# ProPrj_SunLight_2026-07-09.net
KiCad netlist of a schematic drawn in EasyEDA Pro
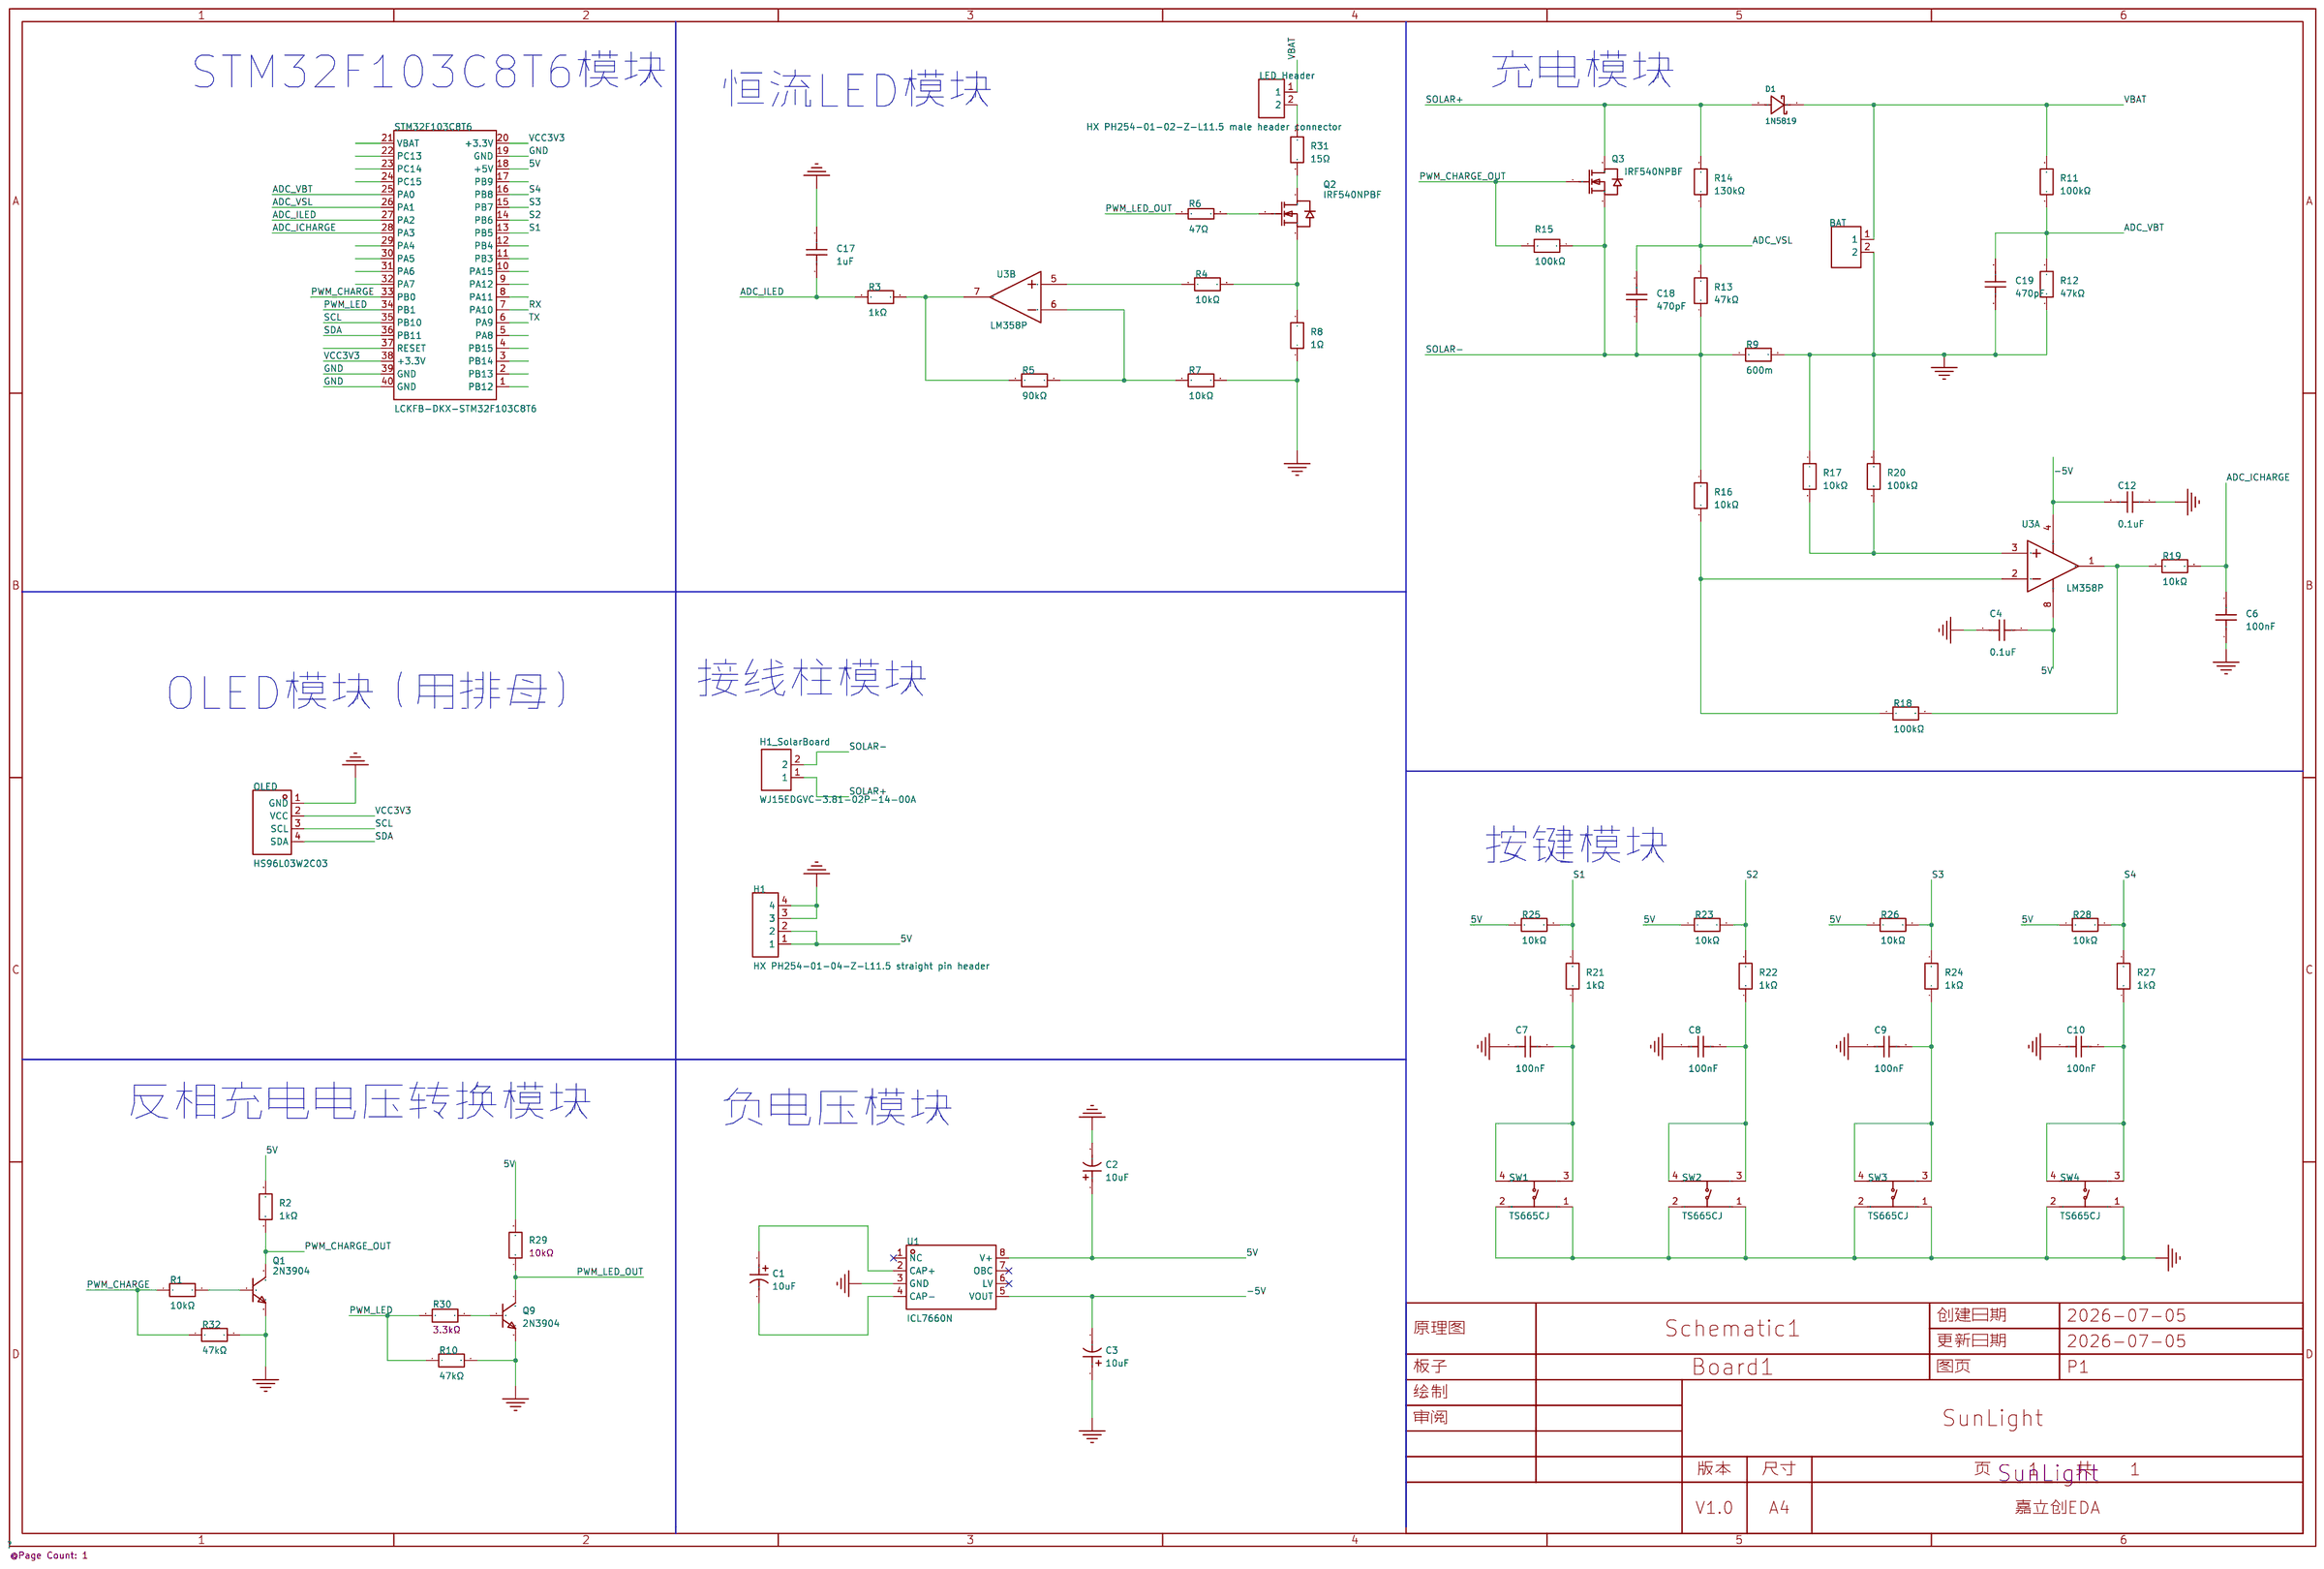
[diagram p0: schematic sheet]

(export (version "E")
  (design (tool "Eeschema 10.0.6"))
  (components
    (comp (ref "BAT")
      (value "WJ15EDGVC-3.81-02P-14-00A")
      (footprint "easyedapro:CONN-TH_WJ15EDGVC-3.81-2P")
      (fields (field (name "Manufacturer") "KANGNEX(康奈克斯电气)"))
      (libsource (lib "easyedapro") (part "WJ15EDGVC-3.81-2P"))
    )
    (comp (ref "C1")
      (value "10uF")
      (footprint "easyedapro:CAP-TH_BD10.0-P5.00-D0.6-FD_1")
      (fields (field (name "Manufacturer Part") "ERG450V10M10x16") (field (name "Manufacturer") "JIERR(捷而瑞)"))
      (libsource (lib "easyedapro") (part "ERG450V10M10X16"))
    )
    (comp (ref "C2")
      (value "10uF")
      (footprint "easyedapro:CAP-TH_BD10.0-P5.00-D0.6-FD_1")
      (fields (field (name "Manufacturer Part") "ERG450V10M10x16") (field (name "Manufacturer") "JIERR(捷而瑞)"))
      (libsource (lib "easyedapro") (part "ERG450V10M10X16"))
    )
    (comp (ref "C3")
      (value "10uF")
      (footprint "easyedapro:CAP-TH_BD10.0-P5.00-D0.6-FD_1")
      (fields (field (name "Manufacturer Part") "ERG450V10M10x16") (field (name "Manufacturer") "JIERR(捷而瑞)"))
      (libsource (lib "easyedapro") (part "ERG450V10M10X16"))
    )
    (comp (ref "C4")
      (value "0.1uF")
      (footprint "easyedapro:CAP-TH_L5.3-W3.2-P2.54-D0.6-S2.65")
      (description "容值:100nF;精度:-20%~+80%;额定电压:50V;温度系数:Y5V;")
      (fields
        (field (name "Manufacturer Part") "CC1H104ZA1ED3F5O1100")
        (field (name "Manufacturer") "Dersonic(德尔创)")
      )
      (libsource (lib "easyedapro") (part "CC1H104ZA1ED3F5O1100"))
    )
    (comp (ref "C6")
      (value "100nF")
      (footprint "easyedapro:CAP-TH_L5.5-W4.0-P5.00-D0.5")
      (fields
        (field (name "Manufacturer Part") "Y5P102K2KV16CC0224")
        (field (name "Manufacturer") "KNSCHA(科尼盛)")
      )
      (libsource (lib "easyedapro") (part "Y5P102K2KV16CC0224"))
    )
    (comp (ref "C7")
      (value "100nF")
      (footprint "easyedapro:CAP-TH_L5.5-W4.0-P5.00-D0.5")
      (fields
        (field (name "Manufacturer Part") "Y5P102K2KV16CC0224")
        (field (name "Manufacturer") "KNSCHA(科尼盛)")
      )
      (libsource (lib "easyedapro") (part "Y5P102K2KV16CC0224"))
    )
    (comp (ref "C8")
      (value "100nF")
      (footprint "easyedapro:CAP-TH_L5.5-W4.0-P5.00-D0.5")
      (fields
        (field (name "Manufacturer Part") "Y5P102K2KV16CC0224")
        (field (name "Manufacturer") "KNSCHA(科尼盛)")
      )
      (libsource (lib "easyedapro") (part "Y5P102K2KV16CC0224"))
    )
    (comp (ref "C9")
      (value "100nF")
      (footprint "easyedapro:CAP-TH_L5.5-W4.0-P5.00-D0.5")
      (fields
        (field (name "Manufacturer Part") "Y5P102K2KV16CC0224")
        (field (name "Manufacturer") "KNSCHA(科尼盛)")
      )
      (libsource (lib "easyedapro") (part "Y5P102K2KV16CC0224"))
    )
    (comp (ref "C10")
      (value "100nF")
      (footprint "easyedapro:CAP-TH_L5.5-W4.0-P5.00-D0.5")
      (fields
        (field (name "Manufacturer Part") "Y5P102K2KV16CC0224")
        (field (name "Manufacturer") "KNSCHA(科尼盛)")
      )
      (libsource (lib "easyedapro") (part "Y5P102K2KV16CC0224"))
    )
    (comp (ref "C12")
      (value "0.1uF")
      (footprint "easyedapro:CAP-TH_L5.3-W3.2-P2.54-D0.6-S2.65")
      (description "容值:100nF;精度:-20%~+80%;额定电压:50V;温度系数:Y5V;")
      (fields
        (field (name "Manufacturer Part") "CC1H104ZA1ED3F5O1100")
        (field (name "Manufacturer") "Dersonic(德尔创)")
      )
      (libsource (lib "easyedapro") (part "CC1H104ZA1ED3F5O1100"))
    )
    (comp (ref "C17")
      (value "1uF")
      (footprint "easyedapro:CAP-TH_L5.8-W2.8")
      (fields
        (field (name "Manufacturer Part") "CC1H104MC1FD3F6C10SA")
        (field (name "Manufacturer") "Dersonic(德尔创)")
      )
      (libsource (lib "easyedapro") (part "CC1H104MC1FD3F6C10SA"))
    )
    (comp (ref "C18")
      (value "470pF")
      (footprint "easyedapro:CAP-TH_L8.0-W4.5-P10.00-D1.2")
      (fields (field (name "Manufacturer Part") "A09B1D471KN0B0S0N0") (field (name "Manufacturer") "STE(松田)"))
      (libsource (lib "easyedapro") (part "A09B1D471KN0B0S0N0"))
    )
    (comp (ref "C19")
      (value "470pF")
      (footprint "easyedapro:CAP-TH_L5.5-W4.0-P5.00-D0.5")
      (fields
        (field (name "Manufacturer Part") "Y5P102K2KV16CC0224")
        (field (name "Manufacturer") "KNSCHA(科尼盛)")
      )
      (libsource (lib "easyedapro") (part "Y5P102K2KV16CC0224"))
    )
    (comp (ref "D1")
      (value "1N5819")
      (footprint "easyedapro:DO-41_BD2.4-L4.7-P8.70-D0.9-RD")
      (fields (field (name "Manufacturer") "R+O(宏嘉诚)"))
      (libsource (lib "easyedapro") (part "1N5819_C54795756"))
    )
    (comp (ref "H1")
      (value "HX PH254-01-04-Z-L11.5 straight pin header")
      (footprint "easyedapro:HDR-TH_4P-HX-PH254-01-04-Z-L11.5")
      (fields (field (name "Manufacturer") "hanxia(韩下)"))
      (libsource (lib "easyedapro") (part "HX PH254-01-04-Z-L11.5 STRAIGHT PIN HEADER"))
    )
    (comp (ref "H1_SolarBoard")
      (value "WJ15EDGVC-3.81-02P-14-00A")
      (footprint "easyedapro:CONN-TH_WJ15EDGVC-3.81-2P")
      (fields (field (name "Manufacturer") "KANGNEX(康奈克斯电气)"))
      (libsource (lib "easyedapro") (part "WJ15EDGVC-3.81-2P"))
    )
    (comp (ref "LED_Header")
      (value "HX PH254-01-02-Z-L11.5 male header connector")
      (footprint "easyedapro:HDR-TH_2P-P2.54-V-M")
      (fields (field (name "Manufacturer") "hanxia(韩下)"))
      (libsource (lib "easyedapro") (part "HX PH254-01-02-Z-L11.5 MALE HEADER CONNECTOR"))
    )
    (comp (ref "OLED")
      (value "HS96L03W2C03")
      (footprint "easyedapro:OLED-TH_L27.8-W27.2-P2.54_C9900033791")
      (description "核心芯片:SSD1315芯片;接口类型:I2C;尺寸(inch):0.96;像素分辨率:128x64;")
      (fields (field (name "Manufacturer") "HS(汉昇)"))
      (libsource (lib "easyedapro") (part "HS96L03W2C03"))
    )
    (comp (ref "Q1")
      (value "2N3904")
      (footprint "easyedapro:TO-92-3_L4.6-W3.6-P1.27-L_1")
      (fields (field (name "Manufacturer") "JSMSEMI(杰盛微)"))
      (libsource (lib "easyedapro") (part "2N3904_C2874602"))
    )
    (comp (ref "Q2")
      (value "IRF540NPBF")
      (footprint "easyedapro:TO-220-3_L10.0-W4.5-P2.54-L")
      (fields (field (name "Manufacturer") "Infineon(英飞凌)"))
      (libsource (lib "easyedapro") (part "IRF540NPBF"))
    )
    (comp (ref "Q3")
      (value "IRF540NPBF")
      (footprint "easyedapro:TO-220-3_L10.0-W4.5-P2.54-L")
      (fields (field (name "Manufacturer") "Infineon(英飞凌)"))
      (libsource (lib "easyedapro") (part "IRF540NPBF"))
    )
    (comp (ref "Q9")
      (value "2N3904")
      (footprint "easyedapro:TO-92-3_L4.6-W3.6-P1.27-L_1")
      (description "晶体管类型:NPN;集电极电流(Ic):200mA;集射极击穿电压(Vceo):40V;耗散功率(Pd):625mW;直流电流增益(hFE):-;")
      (fields (field (name "Manufacturer") "JSMSEMI(杰盛微)"))
      (libsource (lib "easyedapro") (part "2N3904_C2874602"))
    )
    (comp (ref "R1")
      (value "10kΩ")
      (footprint "easyedapro:RES-TH_BD2.7-L6.2-P10.20-D0.4")
      (description "电阻类型:金属膜电阻;阻值:1kΩ;精度:±1%;功率:250mW;温度系数:±100ppm/℃;")
      (fields (field (name "Manufacturer Part") "MF1/4W-1K±1%-ST52") (field (name "Manufacturer") "VO(翔胜)"))
      (libsource (lib "easyedapro") (part "MF1/4W-1K±1%-ST52"))
    )
    (comp (ref "R2")
      (value "1kΩ")
      (footprint "easyedapro:RES-TH_BD2.7-L6.2-P10.20-D0.4")
      (description "电阻类型:金属膜电阻;阻值:1kΩ;精度:±1%;功率:250mW;温度系数:±100ppm/℃;")
      (fields (field (name "Manufacturer Part") "MF1/4W-1K±1%-ST52") (field (name "Manufacturer") "VO(翔胜)"))
      (libsource (lib "easyedapro") (part "MF1/4W-1K±1%-ST52"))
    )
    (comp (ref "R3")
      (value "1kΩ")
      (footprint "easyedapro:RES-TH_BD2.7-L6.2-P10.20-D0.4")
      (description "电阻类型:金属膜电阻;阻值:1kΩ;精度:±1%;功率:250mW;温度系数:±100ppm/℃;")
      (fields (field (name "Manufacturer Part") "MF1/4W-1K±1%-ST52") (field (name "Manufacturer") "VO(翔胜)"))
      (libsource (lib "easyedapro") (part "MF1/4W-1K±1%-ST52"))
    )
    (comp (ref "R4")
      (value "10kΩ")
      (footprint "easyedapro:RES-TH_BD2.7-L6.2-P10.20-D0.4")
      (description "电阻类型:金属膜电阻;阻值:1kΩ;精度:±1%;功率:250mW;温度系数:±100ppm/℃;")
      (fields (field (name "Manufacturer Part") "MF1/4W-1K±1%-ST52") (field (name "Manufacturer") "VO(翔胜)"))
      (libsource (lib "easyedapro") (part "MF1/4W-1K±1%-ST52"))
    )
    (comp (ref "R5")
      (value "90kΩ")
      (footprint "easyedapro:RES-TH_BD2.7-L6.2-P10.20-D0.4")
      (description "电阻类型:金属膜电阻;阻值:1kΩ;精度:±1%;功率:250mW;温度系数:±100ppm/℃;")
      (fields (field (name "Manufacturer Part") "MF1/4W-1K±1%-ST52") (field (name "Manufacturer") "VO(翔胜)"))
      (libsource (lib "easyedapro") (part "MF1/4W-1K±1%-ST52"))
    )
    (comp (ref "R6")
      (value "47Ω")
      (footprint "easyedapro:RES-TH_BD2.4-L6.3-P10.30-D0.6")
      (fields (field (name "Manufacturer Part") "MFR-25FTE52-47R") (field (name "Manufacturer") "YAGEO(国巨)"))
      (libsource (lib "easyedapro") (part "MFR-25FTE52-47R"))
    )
    (comp (ref "R7")
      (value "10kΩ")
      (footprint "easyedapro:RES-TH_BD2.7-L6.2-P10.20-D0.4")
      (description "电阻类型:金属膜电阻;阻值:1kΩ;精度:±1%;功率:250mW;温度系数:±100ppm/℃;")
      (fields (field (name "Manufacturer Part") "MF1/4W-1K±1%-ST52") (field (name "Manufacturer") "VO(翔胜)"))
      (libsource (lib "easyedapro") (part "MF1/4W-1K±1%-ST52"))
    )
    (comp (ref "R8")
      (value "1Ω")
      (footprint "easyedapro:RES-TH_BD2.7-L6.2-P10.20-D0.4")
      (description "电阻类型:金属膜电阻;阻值:1kΩ;精度:±1%;功率:250mW;温度系数:±100ppm/℃;")
      (fields (field (name "Manufacturer Part") "MF1/4W-1K±1%-ST52") (field (name "Manufacturer") "VO(翔胜)"))
      (libsource (lib "easyedapro") (part "MF1/4W-1K±1%-ST52"))
    )
    (comp (ref "R9")
      (value "600m")
      (footprint "easyedapro:RES-TH_BD2.7-L6.2-P10.20-D0.4")
      (description "电阻类型:金属膜电阻;阻值:1kΩ;精度:±1%;功率:250mW;温度系数:±100ppm/℃;")
      (fields (field (name "Manufacturer Part") "MF1/4W-1K±1%-ST52") (field (name "Manufacturer") "VO(翔胜)"))
      (libsource (lib "easyedapro") (part "MF1/4W-1K±1%-ST52"))
    )
    (comp (ref "R10")
      (value "47kΩ")
      (footprint "easyedapro:RES-TH_BD2.7-L6.2-P10.20-D0.4")
      (fields (field (name "Manufacturer Part") "MF1/4W-47K±1%-ST52") (field (name "Manufacturer") "VO(翔胜)"))
      (libsource (lib "easyedapro") (part "MF1/4W-47K±1%-ST52"))
    )
    (comp (ref "R11")
      (value "100kΩ")
      (footprint "easyedapro:RES-TH_BD2.7-L6.2-P10.20-D0.4")
      (description "电阻类型:金属膜电阻;阻值:1kΩ;精度:±1%;功率:250mW;温度系数:±100ppm/℃;")
      (fields (field (name "Manufacturer Part") "MF1/4W-1K±1%-ST52") (field (name "Manufacturer") "VO(翔胜)"))
      (libsource (lib "easyedapro") (part "MF1/4W-1K±1%-ST52"))
    )
    (comp (ref "R12")
      (value "47kΩ")
      (footprint "easyedapro:RES-TH_BD2.7-L6.2-P10.20-D0.4")
      (description "电阻类型:金属膜电阻;阻值:1kΩ;精度:±1%;功率:250mW;温度系数:±100ppm/℃;")
      (fields (field (name "Manufacturer Part") "MF1/4W-1K±1%-ST52") (field (name "Manufacturer") "VO(翔胜)"))
      (libsource (lib "easyedapro") (part "MF1/4W-1K±1%-ST52"))
    )
    (comp (ref "R13")
      (value "47kΩ")
      (footprint "easyedapro:RES-TH_BD2.7-L6.2-P10.20-D0.4")
      (description "电阻类型:金属膜电阻;阻值:1kΩ;精度:±1%;功率:250mW;温度系数:±100ppm/℃;")
      (fields (field (name "Manufacturer Part") "MF1/4W-1K±1%-ST52") (field (name "Manufacturer") "VO(翔胜)"))
      (libsource (lib "easyedapro") (part "MF1/4W-1K±1%-ST52"))
    )
    (comp (ref "R14")
      (value "130kΩ")
      (footprint "easyedapro:RES-TH_BD2.7-L6.2-P10.20-D0.4")
      (description "电阻类型:金属膜电阻;阻值:1kΩ;精度:±1%;功率:250mW;温度系数:±100ppm/℃;")
      (fields (field (name "Manufacturer Part") "MF1/4W-1K±1%-ST52") (field (name "Manufacturer") "VO(翔胜)"))
      (libsource (lib "easyedapro") (part "MF1/4W-1K±1%-ST52"))
    )
    (comp (ref "R15")
      (value "100kΩ")
      (footprint "easyedapro:RES-TH_BD2.7-L6.2-P10.20-D0.4")
      (description "电阻类型:金属膜电阻;阻值:1kΩ;精度:±1%;功率:250mW;温度系数:±100ppm/℃;")
      (fields (field (name "Manufacturer Part") "MF1/4W-1K±1%-ST52") (field (name "Manufacturer") "VO(翔胜)"))
      (libsource (lib "easyedapro") (part "MF1/4W-1K±1%-ST52"))
    )
    (comp (ref "R16")
      (value "10kΩ")
      (footprint "easyedapro:RES-TH_BD2.7-L6.2-P10.20-D0.4")
      (description "电阻类型:金属膜电阻;阻值:1kΩ;精度:±1%;功率:250mW;温度系数:±100ppm/℃;")
      (fields (field (name "Manufacturer Part") "MF1/4W-1K±1%-ST52") (field (name "Manufacturer") "VO(翔胜)"))
      (libsource (lib "easyedapro") (part "MF1/4W-1K±1%-ST52"))
    )
    (comp (ref "R17")
      (value "10kΩ")
      (footprint "easyedapro:RES-TH_BD2.7-L6.2-P10.20-D0.4")
      (description "电阻类型:金属膜电阻;阻值:1kΩ;精度:±1%;功率:250mW;温度系数:±100ppm/℃;")
      (fields (field (name "Manufacturer Part") "MF1/4W-1K±1%-ST52") (field (name "Manufacturer") "VO(翔胜)"))
      (libsource (lib "easyedapro") (part "MF1/4W-1K±1%-ST52"))
    )
    (comp (ref "R18")
      (value "100kΩ")
      (footprint "easyedapro:RES-TH_BD2.7-L6.2-P10.20-D0.4")
      (description "电阻类型:金属膜电阻;阻值:1kΩ;精度:±1%;功率:250mW;温度系数:±100ppm/℃;")
      (fields (field (name "Manufacturer Part") "MF1/4W-1K±1%-ST52") (field (name "Manufacturer") "VO(翔胜)"))
      (libsource (lib "easyedapro") (part "MF1/4W-1K±1%-ST52"))
    )
    (comp (ref "R19")
      (value "10kΩ")
      (footprint "easyedapro:RES-TH_BD2.7-L6.2-P10.20-D0.4")
      (description "电阻类型:金属膜电阻;阻值:1kΩ;精度:±1%;功率:250mW;温度系数:±100ppm/℃;")
      (fields (field (name "Manufacturer Part") "MF1/4W-1K±1%-ST52") (field (name "Manufacturer") "VO(翔胜)"))
      (libsource (lib "easyedapro") (part "MF1/4W-1K±1%-ST52"))
    )
    (comp (ref "R20")
      (value "100kΩ")
      (footprint "easyedapro:RES-TH_BD2.7-L6.2-P10.20-D0.4")
      (description "电阻类型:金属膜电阻;阻值:1kΩ;精度:±1%;功率:250mW;温度系数:±100ppm/℃;")
      (fields (field (name "Manufacturer Part") "MF1/4W-1K±1%-ST52") (field (name "Manufacturer") "VO(翔胜)"))
      (libsource (lib "easyedapro") (part "MF1/4W-1K±1%-ST52"))
    )
    (comp (ref "R21")
      (value "1kΩ")
      (footprint "easyedapro:RES-TH_BD2.7-L6.2-P10.20-D0.4")
      (description "电阻类型:金属膜电阻;阻值:1kΩ;精度:±1%;功率:250mW;温度系数:±100ppm/℃;")
      (fields (field (name "Manufacturer Part") "MF1/4W-1K±1%-ST52") (field (name "Manufacturer") "VO(翔胜)"))
      (libsource (lib "easyedapro") (part "MF1/4W-1K±1%-ST52"))
    )
    (comp (ref "R22")
      (value "1kΩ")
      (footprint "easyedapro:RES-TH_BD2.7-L6.2-P10.20-D0.4")
      (description "电阻类型:金属膜电阻;阻值:1kΩ;精度:±1%;功率:250mW;温度系数:±100ppm/℃;")
      (fields (field (name "Manufacturer Part") "MF1/4W-1K±1%-ST52") (field (name "Manufacturer") "VO(翔胜)"))
      (libsource (lib "easyedapro") (part "MF1/4W-1K±1%-ST52"))
    )
    (comp (ref "R23")
      (value "10kΩ")
      (footprint "easyedapro:RES-TH_BD2.7-L6.2-P10.20-D0.4")
      (description "电阻类型:金属膜电阻;阻值:1kΩ;精度:±1%;功率:250mW;温度系数:±100ppm/℃;")
      (fields (field (name "Manufacturer Part") "MF1/4W-1K±1%-ST52") (field (name "Manufacturer") "VO(翔胜)"))
      (libsource (lib "easyedapro") (part "MF1/4W-1K±1%-ST52"))
    )
    (comp (ref "R24")
      (value "1kΩ")
      (footprint "easyedapro:RES-TH_BD2.7-L6.2-P10.20-D0.4")
      (description "电阻类型:金属膜电阻;阻值:1kΩ;精度:±1%;功率:250mW;温度系数:±100ppm/℃;")
      (fields (field (name "Manufacturer Part") "MF1/4W-1K±1%-ST52") (field (name "Manufacturer") "VO(翔胜)"))
      (libsource (lib "easyedapro") (part "MF1/4W-1K±1%-ST52"))
    )
    (comp (ref "R25")
      (value "10kΩ")
      (footprint "easyedapro:RES-TH_BD2.7-L6.2-P10.20-D0.4")
      (description "电阻类型:金属膜电阻;阻值:1kΩ;精度:±1%;功率:250mW;温度系数:±100ppm/℃;")
      (fields (field (name "Manufacturer Part") "MF1/4W-1K±1%-ST52") (field (name "Manufacturer") "VO(翔胜)"))
      (libsource (lib "easyedapro") (part "MF1/4W-1K±1%-ST52"))
    )
    (comp (ref "R26")
      (value "10kΩ")
      (footprint "easyedapro:RES-TH_BD2.7-L6.2-P10.20-D0.4")
      (description "电阻类型:金属膜电阻;阻值:1kΩ;精度:±1%;功率:250mW;温度系数:±100ppm/℃;")
      (fields (field (name "Manufacturer Part") "MF1/4W-1K±1%-ST52") (field (name "Manufacturer") "VO(翔胜)"))
      (libsource (lib "easyedapro") (part "MF1/4W-1K±1%-ST52"))
    )
    (comp (ref "R27")
      (value "1kΩ")
      (footprint "easyedapro:RES-TH_BD2.7-L6.2-P10.20-D0.4")
      (description "电阻类型:金属膜电阻;阻值:1kΩ;精度:±1%;功率:250mW;温度系数:±100ppm/℃;")
      (fields (field (name "Manufacturer Part") "MF1/4W-1K±1%-ST52") (field (name "Manufacturer") "VO(翔胜)"))
      (libsource (lib "easyedapro") (part "MF1/4W-1K±1%-ST52"))
    )
    (comp (ref "R28")
      (value "10kΩ")
      (footprint "easyedapro:RES-TH_BD2.7-L6.2-P10.20-D0.4")
      (description "电阻类型:金属膜电阻;阻值:1kΩ;精度:±1%;功率:250mW;温度系数:±100ppm/℃;")
      (fields (field (name "Manufacturer Part") "MF1/4W-1K±1%-ST52") (field (name "Manufacturer") "VO(翔胜)"))
      (libsource (lib "easyedapro") (part "MF1/4W-1K±1%-ST52"))
    )
    (comp (ref "R29")
      (value "1kΩ")
      (footprint "easyedapro:RES-TH_BD2.7-L6.2-P10.20-D0.4")
      (description "电阻类型:金属膜电阻;阻值:1kΩ;精度:±1%;功率:250mW;温度系数:±100ppm/℃;")
      (fields
        (field (name "Manufacturer Part") "MF1/4W-1K±1%-ST52")
        (field (name "Manufacturer") "VO(翔胜)")
        (field (name "Resistance") "10kΩ")
      )
      (libsource (lib "easyedapro") (part "MF1/4W-1K±1%-ST52"))
    )
    (comp (ref "R30")
      (value "1kΩ")
      (footprint "easyedapro:RES-TH_BD2.7-L6.2-P10.20-D0.4")
      (description "电阻类型:金属膜电阻;阻值:1kΩ;精度:±1%;功率:250mW;温度系数:±100ppm/℃;")
      (fields
        (field (name "Manufacturer Part") "MF1/4W-1K±1%-ST52")
        (field (name "Manufacturer") "VO(翔胜)")
        (field (name "Resistance") "3.3kΩ")
      )
      (libsource (lib "easyedapro") (part "MF1/4W-1K±1%-ST52"))
    )
    (comp (ref "R31")
      (value "15Ω")
      (footprint "easyedapro:RES-TH_BD2.7-L6.2-P10.20-D0.4")
      (fields (field (name "Manufacturer Part") "MF1/4W-4Ω7±1%-OT26") (field (name "Manufacturer") "VO(翔胜)"))
      (libsource (lib "easyedapro") (part "MF1/4W-4Ω7±1%-OT26"))
    )
    (comp (ref "R32")
      (value "47kΩ")
      (footprint "easyedapro:RES-TH_BD2.7-L6.2-P10.20-D0.4")
      (fields (field (name "Manufacturer Part") "MF1/4W-47K±1%-ST52") (field (name "Manufacturer") "VO(翔胜)"))
      (libsource (lib "easyedapro") (part "MF1/4W-47K±1%-ST52"))
    )
    (comp (ref "STM32F103C8T6")
      (value "LCKFB-DKX-STM32F103C8T6")
      (footprint "easyedapro:CONN-TH_L53.3-W22.9_STM32F103C8T6-CARD")
      (fields (field (name "Manufacturer") "立创开发板"))
      (libsource (lib "easyedapro") (part "LCKFB-DKX-STM32F103C8T6"))
    )
    (comp (ref "SW1")
      (value "TS665CJ")
      (footprint "easyedapro:SW-TH_4P-L6.0-W6.0-P4.50-LS6.5")
      (fields (field (name "Manufacturer") "SHOU HAN(首韩)"))
      (libsource (lib "easyedapro") (part "TS665CJ"))
    )
    (comp (ref "SW2")
      (value "TS665CJ")
      (footprint "easyedapro:SW-TH_4P-L6.0-W6.0-P4.50-LS6.5")
      (fields (field (name "Manufacturer") "SHOU HAN(首韩)"))
      (libsource (lib "easyedapro") (part "TS665CJ"))
    )
    (comp (ref "SW3")
      (value "TS665CJ")
      (footprint "easyedapro:SW-TH_4P-L6.0-W6.0-P4.50-LS6.5")
      (fields (field (name "Manufacturer") "SHOU HAN(首韩)"))
      (libsource (lib "easyedapro") (part "TS665CJ"))
    )
    (comp (ref "SW4")
      (value "TS665CJ")
      (footprint "easyedapro:SW-TH_4P-L6.0-W6.0-P4.50-LS6.5")
      (fields (field (name "Manufacturer") "SHOU HAN(首韩)"))
      (libsource (lib "easyedapro") (part "TS665CJ"))
    )
    (comp (ref "U1")
      (value "ICL7660N")
      (footprint "easyedapro:DIP-8_L9.4-W6.4-P2.54-LS9.1-BL")
      (fields (field (name "Manufacturer") "HGSEMI(华冠)"))
      (libsource (lib "easyedapro") (part "ICL7660N"))
    )
    (comp (ref "U3")
      (value "LM358P")
      (footprint "easyedapro:DIP-8_L9.7-W6.4-P2.54-LS7.6-BL")
      (description "放大器数:2;轨到轨:-;增益带宽积(GBW):1MHz;输入失调电压(Vos):2mV;压摆率(SR):-;输入偏置电流(Ib):45nA;")
      (fields (field (name "Manufacturer") "Slkor(萨科微)"))
      (libsource (lib "easyedapro") (part "LM358P_C5330384"))
    )
  )
  (nets
    (net (code "1") (name "/-5V") (class "Default")
      (node (ref "C12") (pin "2") (pinfunction "2_2") (pintype "unspecified"))
      (node (ref "C3") (pin "2") (pinfunction "2_2") (pintype "input"))
      (node (ref "U1") (pin "5") (pinfunction "VOUT_5") (pintype "unspecified"))
      (node (ref "U3") (pin "4") (pinfunction "GND_4") (pintype "unspecified"))
    )
    (net (code "2") (name "/5V") (class "Default")
      (node (ref "C2") (pin "1") (pinfunction "1_1") (pintype "input"))
      (node (ref "C4") (pin "2") (pinfunction "2_2") (pintype "unspecified"))
      (node (ref "H1") (pin "1") (pinfunction "1_1") (pintype "unspecified"))
      (node (ref "H1") (pin "2") (pinfunction "2_2") (pintype "unspecified"))
      (node (ref "R2") (pin "2") (pinfunction "2_2") (pintype "unspecified"))
      (node (ref "R23") (pin "1") (pinfunction "1_1") (pintype "unspecified"))
      (node (ref "R25") (pin "1") (pinfunction "1_1") (pintype "unspecified"))
      (node (ref "R26") (pin "1") (pinfunction "1_1") (pintype "unspecified"))
      (node (ref "R28") (pin "1") (pinfunction "1_1") (pintype "unspecified"))
      (node (ref "R29") (pin "2") (pinfunction "2_2") (pintype "unspecified"))
      (node (ref "STM32F103C8T6") (pin "18") (pinfunction "+5V_18") (pintype "unspecified"))
      (node (ref "U1") (pin "8") (pinfunction "V+_8") (pintype "unspecified"))
      (node (ref "U3") (pin "8") (pinfunction "VCC_8") (pintype "unspecified"))
    )
    (net (code "3") (name "/ADC_ICHARGE") (class "Default")
      (node (ref "C6") (pin "2") (pinfunction "2_2") (pintype "unspecified"))
      (node (ref "R19") (pin "2") (pinfunction "2_2") (pintype "unspecified"))
      (node (ref "STM32F103C8T6") (pin "28") (pinfunction "PA3_28") (pintype "unspecified"))
    )
    (net (code "4") (name "/ADC_ILED") (class "Default")
      (node (ref "C17") (pin "1") (pinfunction "1_1") (pintype "unspecified"))
      (node (ref "R3") (pin "1") (pinfunction "1_1") (pintype "unspecified"))
      (node (ref "STM32F103C8T6") (pin "27") (pinfunction "PA2_27") (pintype "unspecified"))
    )
    (net (code "5") (name "/ADC_VBT") (class "Default")
      (node (ref "C19") (pin "2") (pinfunction "2_2") (pintype "unspecified"))
      (node (ref "R11") (pin "1") (pinfunction "1_1") (pintype "unspecified"))
      (node (ref "R12") (pin "2") (pinfunction "2_2") (pintype "unspecified"))
      (node (ref "STM32F103C8T6") (pin "25") (pinfunction "PA0_25") (pintype "unspecified"))
    )
    (net (code "6") (name "/ADC_VSL") (class "Default")
      (node (ref "C18") (pin "2") (pinfunction "2_2") (pintype "unspecified"))
      (node (ref "R13") (pin "2") (pinfunction "2_2") (pintype "unspecified"))
      (node (ref "R14") (pin "1") (pinfunction "1_1") (pintype "unspecified"))
      (node (ref "STM32F103C8T6") (pin "26") (pinfunction "PA1_26") (pintype "unspecified"))
    )
    (net (code "7") (name "/PWM_CHARGE") (class "Default")
      (node (ref "R1") (pin "1") (pinfunction "1_1") (pintype "unspecified"))
      (node (ref "R32") (pin "1") (pinfunction "1_1") (pintype "unspecified"))
      (node (ref "STM32F103C8T6") (pin "33") (pinfunction "PB0_33") (pintype "unspecified"))
    )
    (net (code "8") (name "/PWM_CHARGE_OUT") (class "Default")
      (node (ref "Q1") (pin "1") (pinfunction "C_1") (pintype "unspecified"))
      (node (ref "Q3") (pin "1") (pinfunction "G_1") (pintype "unspecified"))
      (node (ref "R15") (pin "2") (pinfunction "2_2") (pintype "unspecified"))
      (node (ref "R2") (pin "1") (pinfunction "1_1") (pintype "unspecified"))
    )
    (net (code "9") (name "/PWM_LED") (class "Default")
      (node (ref "R10") (pin "1") (pinfunction "1_1") (pintype "unspecified"))
      (node (ref "R30") (pin "2") (pinfunction "2_2") (pintype "unspecified"))
      (node (ref "STM32F103C8T6") (pin "34") (pinfunction "PB1_34") (pintype "unspecified"))
    )
    (net (code "10") (name "/PWM_LED_OUT") (class "Default")
      (node (ref "Q9") (pin "1") (pinfunction "C_1") (pintype "unspecified"))
      (node (ref "R29") (pin "1") (pinfunction "1_1") (pintype "unspecified"))
      (node (ref "R6") (pin "1") (pinfunction "1_1") (pintype "unspecified"))
    )
    (net (code "11") (name "/RX") (class "Default")
      (node (ref "STM32F103C8T6") (pin "7") (pinfunction "PA10_7") (pintype "unspecified"))
    )
    (net (code "12") (name "/S1") (class "Default")
      (node (ref "R21") (pin "2") (pinfunction "2_2") (pintype "unspecified"))
      (node (ref "R25") (pin "2") (pinfunction "2_2") (pintype "unspecified"))
      (node (ref "STM32F103C8T6") (pin "13") (pinfunction "PB5_13") (pintype "unspecified"))
    )
    (net (code "13") (name "/S2") (class "Default")
      (node (ref "R22") (pin "2") (pinfunction "2_2") (pintype "unspecified"))
      (node (ref "R23") (pin "2") (pinfunction "2_2") (pintype "unspecified"))
      (node (ref "STM32F103C8T6") (pin "14") (pinfunction "PB6_14") (pintype "unspecified"))
    )
    (net (code "14") (name "/S3") (class "Default")
      (node (ref "R24") (pin "2") (pinfunction "2_2") (pintype "unspecified"))
      (node (ref "R26") (pin "2") (pinfunction "2_2") (pintype "unspecified"))
      (node (ref "STM32F103C8T6") (pin "15") (pinfunction "PB7_15") (pintype "unspecified"))
    )
    (net (code "15") (name "/S4") (class "Default")
      (node (ref "R27") (pin "2") (pinfunction "2_2") (pintype "unspecified"))
      (node (ref "R28") (pin "2") (pinfunction "2_2") (pintype "unspecified"))
      (node (ref "STM32F103C8T6") (pin "16") (pinfunction "PB8_16") (pintype "unspecified"))
    )
    (net (code "16") (name "/SCL") (class "Default")
      (node (ref "OLED") (pin "3") (pinfunction "SCL_3") (pintype "unspecified"))
      (node (ref "STM32F103C8T6") (pin "35") (pinfunction "PB10_35") (pintype "unspecified"))
    )
    (net (code "17") (name "/SDA") (class "Default")
      (node (ref "OLED") (pin "4") (pinfunction "SDA_4") (pintype "unspecified"))
      (node (ref "STM32F103C8T6") (pin "36") (pinfunction "PB11_36") (pintype "unspecified"))
    )
    (net (code "18") (name "/SOLAR+") (class "Default")
      (node (ref "D1") (pin "2") (pinfunction "A_2") (pintype "unspecified"))
      (node (ref "H1_SolarBoard") (pin "1") (pinfunction "1_1") (pintype "unspecified"))
      (node (ref "Q3") (pin "2") (pinfunction "D_2") (pintype "unspecified"))
      (node (ref "R14") (pin "2") (pinfunction "2_2") (pintype "unspecified"))
    )
    (net (code "19") (name "/SOLAR-") (class "Default")
      (node (ref "C18") (pin "1") (pinfunction "1_1") (pintype "unspecified"))
      (node (ref "H1_SolarBoard") (pin "2") (pinfunction "2_2") (pintype "unspecified"))
      (node (ref "Q3") (pin "3") (pinfunction "S_3") (pintype "unspecified"))
      (node (ref "R13") (pin "1") (pinfunction "1_1") (pintype "unspecified"))
      (node (ref "R15") (pin "1") (pinfunction "1_1") (pintype "unspecified"))
      (node (ref "R16") (pin "1") (pinfunction "1_1") (pintype "unspecified"))
      (node (ref "R9") (pin "1") (pinfunction "1_1") (pintype "unspecified"))
    )
    (net (code "20") (name "/TX") (class "Default")
      (node (ref "STM32F103C8T6") (pin "6") (pinfunction "PA9_6") (pintype "unspecified"))
    )
    (net (code "21") (name "/VBAT") (class "Default")
      (node (ref "BAT") (pin "1") (pinfunction "1_1") (pintype "unspecified"))
      (node (ref "D1") (pin "1") (pinfunction "C_1") (pintype "unspecified"))
      (node (ref "LED_Header") (pin "1") (pinfunction "1_1") (pintype "unspecified"))
      (node (ref "R11") (pin "2") (pinfunction "2_2") (pintype "unspecified"))
    )
    (net (code "22") (name "/VCC3V3") (class "Default")
      (node (ref "OLED") (pin "2") (pinfunction "VCC_2") (pintype "unspecified"))
      (node (ref "STM32F103C8T6") (pin "20") (pinfunction "+3.3V_20") (pintype "unspecified"))
      (node (ref "STM32F103C8T6") (pin "38") (pinfunction "+3.3V_38") (pintype "unspecified"))
    )
    (net (code "23") (name "GND") (class "Default")
      (node (ref "BAT") (pin "2") (pinfunction "2_2") (pintype "unspecified"))
      (node (ref "C10") (pin "1") (pinfunction "1_1") (pintype "unspecified"))
      (node (ref "C12") (pin "1") (pinfunction "1_1") (pintype "unspecified"))
      (node (ref "C17") (pin "2") (pinfunction "2_2") (pintype "unspecified"))
      (node (ref "C19") (pin "1") (pinfunction "1_1") (pintype "unspecified"))
      (node (ref "C2") (pin "2") (pinfunction "2_2") (pintype "input"))
      (node (ref "C3") (pin "1") (pinfunction "1_1") (pintype "input"))
      (node (ref "C4") (pin "1") (pinfunction "1_1") (pintype "unspecified"))
      (node (ref "C6") (pin "1") (pinfunction "1_1") (pintype "unspecified"))
      (node (ref "C7") (pin "1") (pinfunction "1_1") (pintype "unspecified"))
      (node (ref "C8") (pin "1") (pinfunction "1_1") (pintype "unspecified"))
      (node (ref "C9") (pin "1") (pinfunction "1_1") (pintype "unspecified"))
      (node (ref "H1") (pin "3") (pinfunction "3_3") (pintype "unspecified"))
      (node (ref "H1") (pin "4") (pinfunction "4_4") (pintype "unspecified"))
      (node (ref "OLED") (pin "1") (pinfunction "GND_1") (pintype "unspecified"))
      (node (ref "Q1") (pin "3") (pinfunction "E_3") (pintype "unspecified"))
      (node (ref "Q9") (pin "3") (pinfunction "E_3") (pintype "unspecified"))
      (node (ref "R10") (pin "2") (pinfunction "2_2") (pintype "unspecified"))
      (node (ref "R12") (pin "1") (pinfunction "1_1") (pintype "unspecified"))
      (node (ref "R17") (pin "1") (pinfunction "1_1") (pintype "unspecified"))
      (node (ref "R20") (pin "2") (pinfunction "2_2") (pintype "unspecified"))
      (node (ref "R32") (pin "2") (pinfunction "2_2") (pintype "unspecified"))
      (node (ref "R7") (pin "2") (pinfunction "2_2") (pintype "unspecified"))
      (node (ref "R8") (pin "1") (pinfunction "1_1") (pintype "unspecified"))
      (node (ref "R9") (pin "2") (pinfunction "2_2") (pintype "unspecified"))
      (node (ref "STM32F103C8T6") (pin "19") (pinfunction "GND_19") (pintype "unspecified"))
      (node (ref "STM32F103C8T6") (pin "39") (pinfunction "GND_39") (pintype "unspecified"))
      (node (ref "STM32F103C8T6") (pin "40") (pinfunction "GND_40") (pintype "unspecified"))
      (node (ref "SW1") (pin "1") (pinfunction "A_1") (pintype "unspecified"))
      (node (ref "SW1") (pin "2") (pinfunction "B_2") (pintype "unspecified"))
      (node (ref "SW2") (pin "1") (pinfunction "A_1") (pintype "unspecified"))
      (node (ref "SW2") (pin "2") (pinfunction "B_2") (pintype "unspecified"))
      (node (ref "SW3") (pin "1") (pinfunction "A_1") (pintype "unspecified"))
      (node (ref "SW3") (pin "2") (pinfunction "B_2") (pintype "unspecified"))
      (node (ref "SW4") (pin "1") (pinfunction "A_1") (pintype "unspecified"))
      (node (ref "SW4") (pin "2") (pinfunction "B_2") (pintype "unspecified"))
      (node (ref "U1") (pin "3") (pinfunction "GND_3") (pintype "unspecified"))
    )
    (net (code "24") (name "Net-(LED_Header-Pad2)") (class "Default")
      (node (ref "LED_Header") (pin "2") (pinfunction "2_2") (pintype "unspecified"))
      (node (ref "R31") (pin "2") (pinfunction "2_2") (pintype "unspecified"))
    )
    (net (code "25") (name "Net-(Q1-B)") (class "Default")
      (node (ref "Q1") (pin "2") (pinfunction "B_2") (pintype "unspecified"))
      (node (ref "R1") (pin "2") (pinfunction "2_2") (pintype "unspecified"))
    )
    (net (code "26") (name "Net-(Q2-D)") (class "Default")
      (node (ref "Q2") (pin "2") (pinfunction "D_2") (pintype "unspecified"))
      (node (ref "R31") (pin "1") (pinfunction "1_1") (pintype "unspecified"))
    )
    (net (code "27") (name "Net-(Q2-G)") (class "Default")
      (node (ref "Q2") (pin "1") (pinfunction "G_1") (pintype "unspecified"))
      (node (ref "R6") (pin "2") (pinfunction "2_2") (pintype "unspecified"))
    )
    (net (code "28") (name "Net-(Q2-S)") (class "Default")
      (node (ref "Q2") (pin "3") (pinfunction "S_3") (pintype "unspecified"))
      (node (ref "R4") (pin "2") (pinfunction "2_2") (pintype "unspecified"))
      (node (ref "R8") (pin "2") (pinfunction "2_2") (pintype "unspecified"))
    )
    (net (code "29") (name "Net-(Q9-B)") (class "Default")
      (node (ref "Q9") (pin "2") (pinfunction "B_2") (pintype "unspecified"))
      (node (ref "R30") (pin "1") (pinfunction "1_1") (pintype "unspecified"))
    )
    (net (code "30") (name "Net-(SW1-C)") (class "Default")
      (node (ref "C7") (pin "2") (pinfunction "2_2") (pintype "unspecified"))
      (node (ref "R21") (pin "1") (pinfunction "1_1") (pintype "unspecified"))
      (node (ref "SW1") (pin "3") (pinfunction "C_3") (pintype "unspecified"))
      (node (ref "SW1") (pin "4") (pinfunction "D_4") (pintype "unspecified"))
    )
    (net (code "31") (name "Net-(SW2-C)") (class "Default")
      (node (ref "C8") (pin "2") (pinfunction "2_2") (pintype "unspecified"))
      (node (ref "R22") (pin "1") (pinfunction "1_1") (pintype "unspecified"))
      (node (ref "SW2") (pin "3") (pinfunction "C_3") (pintype "unspecified"))
      (node (ref "SW2") (pin "4") (pinfunction "D_4") (pintype "unspecified"))
    )
    (net (code "32") (name "Net-(SW3-C)") (class "Default")
      (node (ref "C9") (pin "2") (pinfunction "2_2") (pintype "unspecified"))
      (node (ref "R24") (pin "1") (pinfunction "1_1") (pintype "unspecified"))
      (node (ref "SW3") (pin "3") (pinfunction "C_3") (pintype "unspecified"))
      (node (ref "SW3") (pin "4") (pinfunction "D_4") (pintype "unspecified"))
    )
    (net (code "33") (name "Net-(SW4-C)") (class "Default")
      (node (ref "C10") (pin "2") (pinfunction "2_2") (pintype "unspecified"))
      (node (ref "R27") (pin "1") (pinfunction "1_1") (pintype "unspecified"))
      (node (ref "SW4") (pin "3") (pinfunction "C_3") (pintype "unspecified"))
      (node (ref "SW4") (pin "4") (pinfunction "D_4") (pintype "unspecified"))
    )
    (net (code "34") (name "Net-(U1-CAP+)") (class "Default")
      (node (ref "C1") (pin "1") (pinfunction "1_1") (pintype "input"))
      (node (ref "U1") (pin "2") (pinfunction "CAP+_2") (pintype "unspecified"))
    )
    (net (code "35") (name "Net-(U1-CAP-)") (class "Default")
      (node (ref "C1") (pin "2") (pinfunction "2_2") (pintype "input"))
      (node (ref "U1") (pin "4") (pinfunction "CAP-_4") (pintype "unspecified"))
    )
    (net (code "36") (name "Net-(U3A-IN1+)") (class "Default")
      (node (ref "R17") (pin "2") (pinfunction "2_2") (pintype "unspecified"))
      (node (ref "R20") (pin "1") (pinfunction "1_1") (pintype "unspecified"))
      (node (ref "U3") (pin "3") (pinfunction "IN1+_3") (pintype "unspecified"))
    )
    (net (code "37") (name "Net-(U3A-IN1-)") (class "Default")
      (node (ref "R16") (pin "2") (pinfunction "2_2") (pintype "unspecified"))
      (node (ref "R18") (pin "1") (pinfunction "1_1") (pintype "unspecified"))
      (node (ref "U3") (pin "2") (pinfunction "IN1-_2") (pintype "unspecified"))
    )
    (net (code "38") (name "Net-(U3A-OUT1)") (class "Default")
      (node (ref "R18") (pin "2") (pinfunction "2_2") (pintype "unspecified"))
      (node (ref "R19") (pin "1") (pinfunction "1_1") (pintype "unspecified"))
      (node (ref "U3") (pin "1") (pinfunction "OUT1_1") (pintype "output"))
    )
    (net (code "39") (name "Net-(U3B-IN2+)") (class "Default")
      (node (ref "R4") (pin "1") (pinfunction "1_1") (pintype "unspecified"))
      (node (ref "U3") (pin "5") (pinfunction "IN2+_5") (pintype "unspecified"))
    )
    (net (code "40") (name "Net-(U3B-IN2-)") (class "Default")
      (node (ref "R5") (pin "2") (pinfunction "2_2") (pintype "unspecified"))
      (node (ref "R7") (pin "1") (pinfunction "1_1") (pintype "unspecified"))
      (node (ref "U3") (pin "6") (pinfunction "IN2-_6") (pintype "unspecified"))
    )
    (net (code "41") (name "Net-(U3B-OUT2)") (class "Default")
      (node (ref "R3") (pin "2") (pinfunction "2_2") (pintype "unspecified"))
      (node (ref "R5") (pin "1") (pinfunction "1_1") (pintype "unspecified"))
      (node (ref "U3") (pin "7") (pinfunction "OUT2_7") (pintype "output"))
    )
    (net (code "42") (name "unconnected-(STM32F103C8T6-PA4-Pad29)") (class "Default")
      (node (ref "STM32F103C8T6") (pin "29") (pinfunction "PA4_29") (pintype "unspecified"))
    )
    (net (code "43") (name "unconnected-(STM32F103C8T6-PA5-Pad30)") (class "Default")
      (node (ref "STM32F103C8T6") (pin "30") (pinfunction "PA5_30") (pintype "unspecified"))
    )
    (net (code "44") (name "unconnected-(STM32F103C8T6-PA6-Pad31)") (class "Default")
      (node (ref "STM32F103C8T6") (pin "31") (pinfunction "PA6_31") (pintype "unspecified"))
    )
    (net (code "45") (name "unconnected-(STM32F103C8T6-PA7-Pad32)") (class "Default")
      (node (ref "STM32F103C8T6") (pin "32") (pinfunction "PA7_32") (pintype "unspecified"))
    )
    (net (code "46") (name "unconnected-(STM32F103C8T6-PA8-Pad5)") (class "Default")
      (node (ref "STM32F103C8T6") (pin "5") (pinfunction "PA8_5") (pintype "unspecified"))
    )
    (net (code "47") (name "unconnected-(STM32F103C8T6-PA11-Pad8)") (class "Default")
      (node (ref "STM32F103C8T6") (pin "8") (pinfunction "PA11_8") (pintype "unspecified"))
    )
    (net (code "48") (name "unconnected-(STM32F103C8T6-PA12-Pad9)") (class "Default")
      (node (ref "STM32F103C8T6") (pin "9") (pinfunction "PA12_9") (pintype "unspecified"))
    )
    (net (code "49") (name "unconnected-(STM32F103C8T6-PA15-Pad10)") (class "Default")
      (node (ref "STM32F103C8T6") (pin "10") (pinfunction "PA15_10") (pintype "unspecified"))
    )
    (net (code "50") (name "unconnected-(STM32F103C8T6-PB3-Pad11)") (class "Default")
      (node (ref "STM32F103C8T6") (pin "11") (pinfunction "PB3_11") (pintype "unspecified"))
    )
    (net (code "51") (name "unconnected-(STM32F103C8T6-PB4-Pad12)") (class "Default")
      (node (ref "STM32F103C8T6") (pin "12") (pinfunction "PB4_12") (pintype "unspecified"))
    )
    (net (code "52") (name "unconnected-(STM32F103C8T6-PB9-Pad17)") (class "Default")
      (node (ref "STM32F103C8T6") (pin "17") (pinfunction "PB9_17") (pintype "unspecified"))
    )
    (net (code "53") (name "unconnected-(STM32F103C8T6-PB12-Pad1)") (class "Default")
      (node (ref "STM32F103C8T6") (pin "1") (pinfunction "PB12_1") (pintype "unspecified"))
    )
    (net (code "54") (name "unconnected-(STM32F103C8T6-PB13-Pad2)") (class "Default")
      (node (ref "STM32F103C8T6") (pin "2") (pinfunction "PB13_2") (pintype "unspecified"))
    )
    (net (code "55") (name "unconnected-(STM32F103C8T6-PB14-Pad3)") (class "Default")
      (node (ref "STM32F103C8T6") (pin "3") (pinfunction "PB14_3") (pintype "unspecified"))
    )
    (net (code "56") (name "unconnected-(STM32F103C8T6-PB15-Pad4)") (class "Default")
      (node (ref "STM32F103C8T6") (pin "4") (pinfunction "PB15_4") (pintype "unspecified"))
    )
    (net (code "57") (name "unconnected-(STM32F103C8T6-PC13-Pad22)") (class "Default")
      (node (ref "STM32F103C8T6") (pin "22") (pinfunction "PC13_22") (pintype "unspecified"))
    )
    (net (code "58") (name "unconnected-(STM32F103C8T6-PC14-Pad23)") (class "Default")
      (node (ref "STM32F103C8T6") (pin "23") (pinfunction "PC14_23") (pintype "unspecified"))
    )
    (net (code "59") (name "unconnected-(STM32F103C8T6-PC15-Pad24)") (class "Default")
      (node (ref "STM32F103C8T6") (pin "24") (pinfunction "PC15_24") (pintype "unspecified"))
    )
    (net (code "60") (name "unconnected-(STM32F103C8T6-RESET-Pad37)") (class "Default")
      (node (ref "STM32F103C8T6") (pin "37") (pinfunction "RESET_37") (pintype "unspecified"))
    )
    (net (code "61") (name "unconnected-(STM32F103C8T6-VBAT-Pad21)") (class "Default")
      (node (ref "STM32F103C8T6") (pin "21") (pinfunction "VBAT_21") (pintype "unspecified"))
    )
    (net (code "62") (name "unconnected-(U1-LV-Pad6)") (class "Default")
      (node (ref "U1") (pin "6") (pinfunction "LV_6") (pintype "unspecified+no_connect"))
    )
    (net (code "63") (name "unconnected-(U1-NC-Pad1)") (class "Default")
      (node (ref "U1") (pin "1") (pinfunction "NC_1") (pintype "unspecified+no_connect"))
    )
    (net (code "64") (name "unconnected-(U1-OBC-Pad7)") (class "Default")
      (node (ref "U1") (pin "7") (pinfunction "OBC_7") (pintype "unspecified+no_connect"))
    )
  )
)
